# aqm_sch.net
KiCad netlist of a schematic drawn in EAGLE
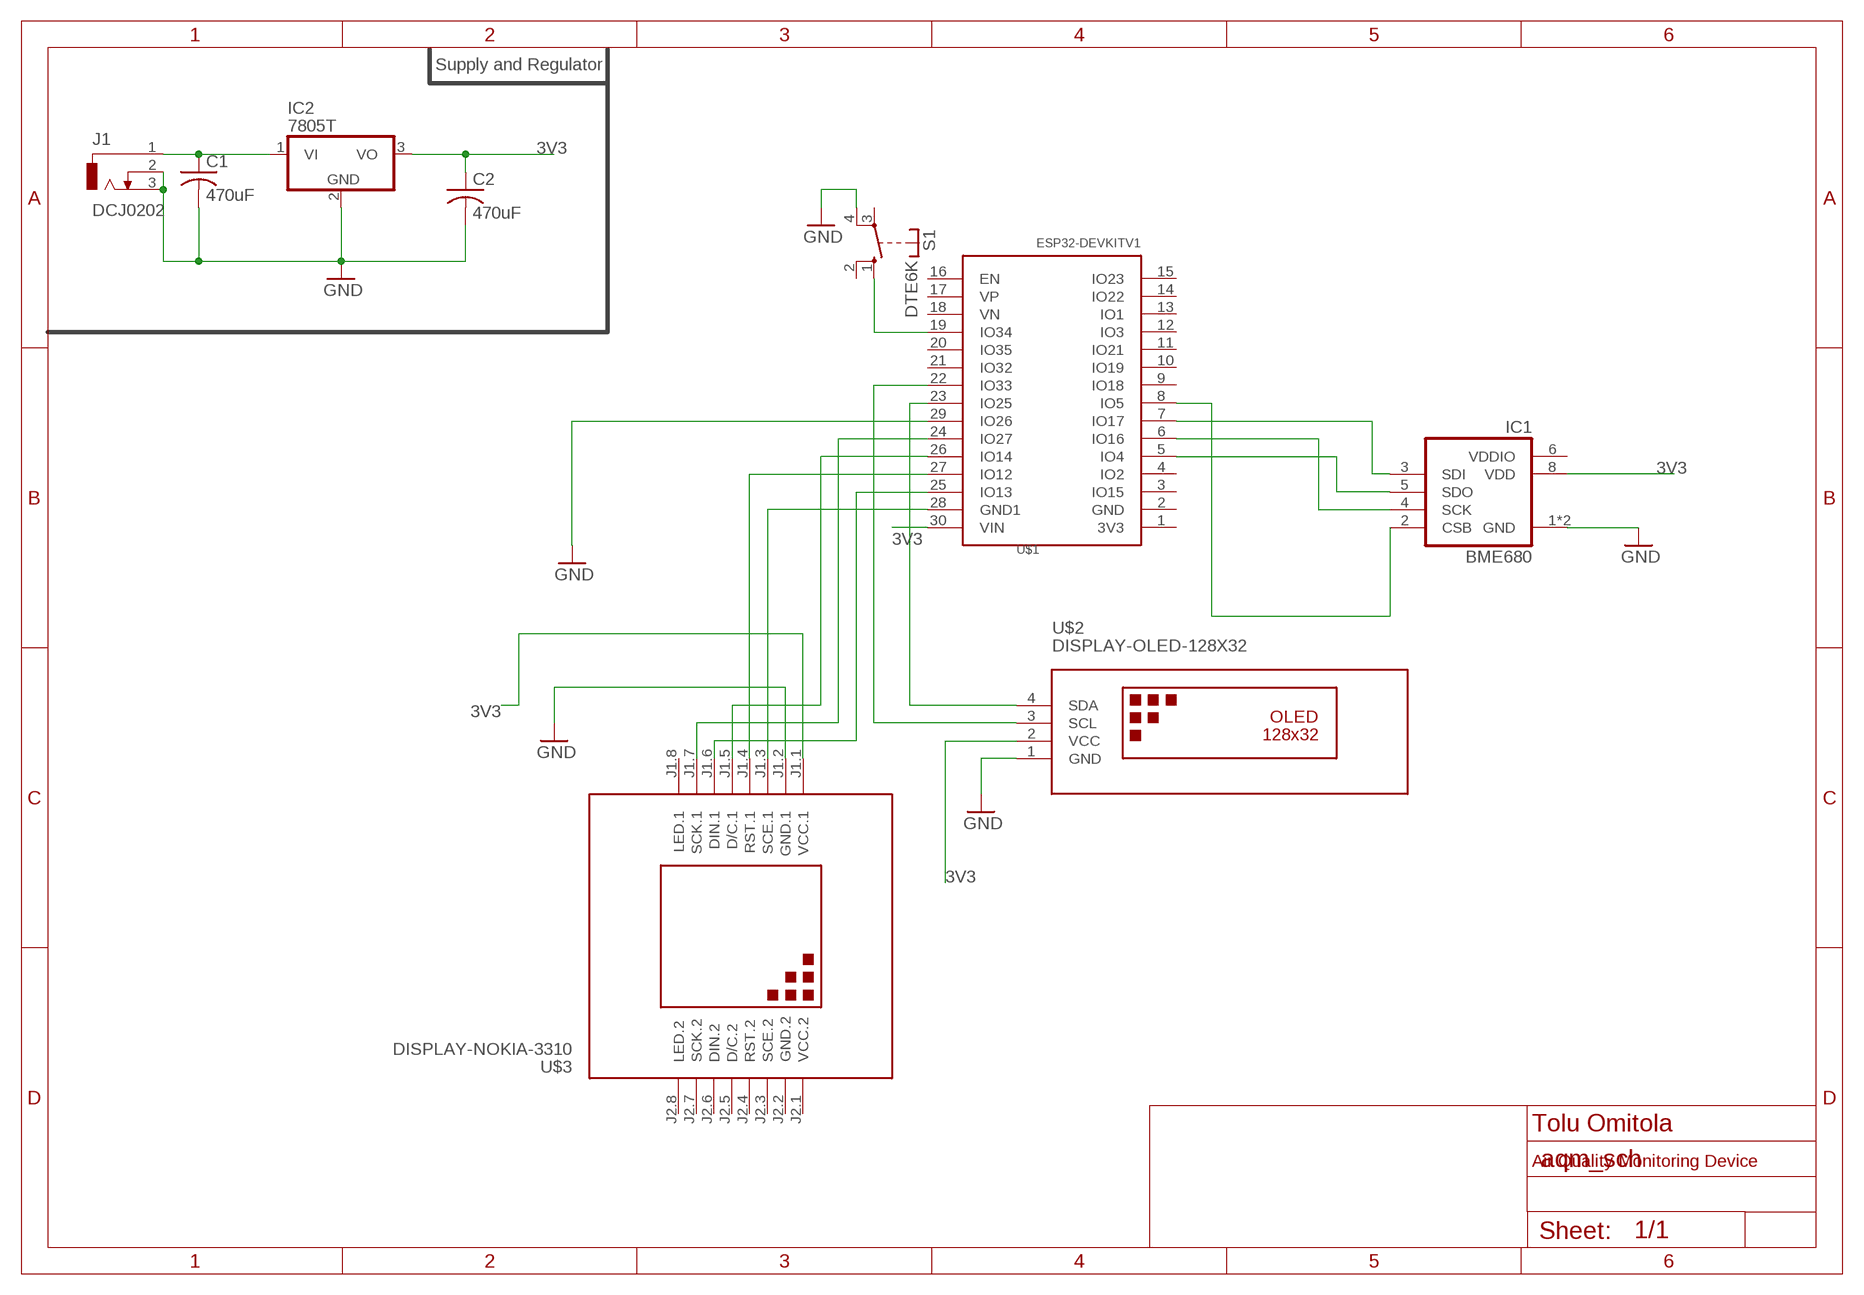
[diagram p0: schematic, sheet 1]

(export (version "E")
  (design (tool "Eeschema 10.0.6"))
  (components
    (comp (ref "C1")
      (value "470uF")
      (footprint "eagle-import:C075-052X106")
      (libsource (lib "eagle-import") (part "C-US075-052X106"))
    )
    (comp (ref "C2")
      (value "470uF")
      (footprint "eagle-import:C075-052X106")
      (libsource (lib "eagle-import") (part "C-US075-052X106"))
    )
    (comp (ref "IC1")
      (value "BME680")
      (footprint "eagle-import:BME680")
      (libsource (lib "eagle-import") (part "BME680"))
    )
    (comp (ref "IC2")
      (value "7805T")
      (footprint "eagle-import:TO220H")
      (libsource (lib "eagle-import") (part "78T05"))
    )
    (comp (ref "J1")
      (value "DCJ0202")
      (footprint "eagle-import:DCJ0202")
      (libsource (lib "eagle-import") (part "DCJ0202"))
    )
    (comp (ref "S1")
      (value "DTE6K")
      (footprint "eagle-import:DTE6K")
      (libsource (lib "eagle-import") (part "DTE6K"))
    )
    (comp (ref "U$1")
      (value "ESP32DEVKITV1")
      (footprint "eagle-import:ESP32-DEVKITV1")
      (libsource (lib "eagle-import") (part "ESP32DEVKITV1"))
    )
    (comp (ref "U$2")
      (value "DISPLAY-OLED-128X32")
      (footprint "eagle-import:DISPLAY-OLED-128X32")
      (libsource (lib "eagle-import") (part "DISPLAY-OLED-128X32"))
    )
    (comp (ref "U$3")
      (value "DISPLAY-NOKIA-3310")
      (footprint "eagle-import:DISPLAY-NOKIA-3310")
      (libsource (lib "eagle-import") (part "DISPLAY-NOKIA-3310"))
    )
  )
  (nets
    (net (code "1") (name "/3V3") (class "Default")
      (node (ref "C2") (pin "1") (pinfunction "1_1") (pintype "passive"))
      (node (ref "IC1") (pin "8") (pinfunction "VDD_8") (pintype "power_in"))
      (node (ref "IC2") (pin "3") (pinfunction "VO_3") (pintype "passive"))
      (node (ref "U$1") (pin "30") (pinfunction "VIN_30") (pintype "bidirectional"))
      (node (ref "U$2") (pin "2") (pinfunction "VCC_2") (pintype "power_in"))
      (node (ref "U$3") (pin "J1.1") (pinfunction "VCC.1_J1.1") (pintype "power_in"))
    )
    (net (code "2") (name "/GND.2") (class "Default")
      (node (ref "U$3") (pin "J2.2") (pinfunction "GND.2_J2.2") (pintype "power_in"))
    )
    (net (code "3") (name "/VCC.2") (class "Default")
      (node (ref "U$3") (pin "J2.1") (pinfunction "VCC.2_J2.1") (pintype "power_in"))
    )
    (net (code "4") (name "/VDDIO") (class "Default")
      (node (ref "IC1") (pin "6") (pinfunction "VDDIO_6") (pintype "power_in"))
    )
    (net (code "5") (name "GND") (class "Default")
      (node (ref "C1") (pin "2") (pinfunction "2_2") (pintype "passive"))
      (node (ref "C2") (pin "2") (pinfunction "2_2") (pintype "passive"))
      (node (ref "IC1") (pin "1") (pinfunction "GND_1") (pintype "power_in"))
      (node (ref "IC1") (pin "7") (pinfunction "GND_7") (pintype "power_in"))
      (node (ref "IC2") (pin "2") (pinfunction "GND_2") (pintype "passive"))
      (node (ref "J1") (pin "2") (pinfunction "2_2") (pintype "passive"))
      (node (ref "J1") (pin "3") (pinfunction "3_3") (pintype "passive"))
      (node (ref "S1") (pin "4") (pinfunction "P_4") (pintype "passive"))
      (node (ref "U$1") (pin "29") (pinfunction "IO26_29") (pintype "bidirectional"))
      (node (ref "U$2") (pin "1") (pinfunction "GND_1") (pintype "power_in"))
      (node (ref "U$3") (pin "J1.2") (pinfunction "GND.1_J1.2") (pintype "power_in"))
    )
    (net (code "6") (name "Net-(IC1-CSB)") (class "Default")
      (node (ref "IC1") (pin "2") (pinfunction "CSB_2") (pintype "input"))
      (node (ref "U$1") (pin "8") (pinfunction "IO5_8") (pintype "bidirectional"))
    )
    (net (code "7") (name "Net-(IC1-SCK)") (class "Default")
      (node (ref "IC1") (pin "4") (pinfunction "SCK_4") (pintype "input"))
      (node (ref "U$1") (pin "6") (pinfunction "IO16_6") (pintype "bidirectional"))
    )
    (net (code "8") (name "Net-(IC1-SDI)") (class "Default")
      (node (ref "IC1") (pin "3") (pinfunction "SDI_3") (pintype "input"))
      (node (ref "U$1") (pin "7") (pinfunction "IO17_7") (pintype "bidirectional"))
    )
    (net (code "9") (name "Net-(IC1-SDO)") (class "Default")
      (node (ref "IC1") (pin "5") (pinfunction "SDO_5") (pintype "output"))
      (node (ref "U$1") (pin "5") (pinfunction "IO4_5") (pintype "bidirectional"))
    )
    (net (code "10") (name "Net-(IC2-VI)") (class "Default")
      (node (ref "C1") (pin "1") (pinfunction "1_1") (pintype "passive"))
      (node (ref "IC2") (pin "1") (pinfunction "VI_1") (pintype "input"))
      (node (ref "J1") (pin "1") (pinfunction "1_1") (pintype "passive"))
    )
    (net (code "11") (name "Net-(U$1-GND1)") (class "Default")
      (node (ref "U$1") (pin "28") (pinfunction "GND1_28") (pintype "bidirectional"))
      (node (ref "U$3") (pin "J1.3") (pinfunction "SCE.1_J1.3") (pintype "bidirectional"))
    )
    (net (code "12") (name "Net-(U$1-IO12)") (class "Default")
      (node (ref "U$1") (pin "27") (pinfunction "IO12_27") (pintype "bidirectional"))
      (node (ref "U$3") (pin "J1.4") (pinfunction "RST.1_J1.4") (pintype "bidirectional"))
    )
    (net (code "13") (name "Net-(U$1-IO13)") (class "Default")
      (node (ref "U$1") (pin "25") (pinfunction "IO13_25") (pintype "bidirectional"))
      (node (ref "U$3") (pin "J1.6") (pinfunction "DIN.1_J1.6") (pintype "bidirectional"))
    )
    (net (code "14") (name "Net-(U$1-IO14)") (class "Default")
      (node (ref "U$1") (pin "26") (pinfunction "IO14_26") (pintype "bidirectional"))
      (node (ref "U$3") (pin "J1.5") (pinfunction "D/C.1_J1.5") (pintype "bidirectional"))
    )
    (net (code "15") (name "Net-(U$1-IO25)") (class "Default")
      (node (ref "U$1") (pin "23") (pinfunction "IO25_23") (pintype "bidirectional"))
      (node (ref "U$2") (pin "4") (pinfunction "SDA_4") (pintype "bidirectional"))
    )
    (net (code "16") (name "Net-(U$1-IO27)") (class "Default")
      (node (ref "U$1") (pin "24") (pinfunction "IO27_24") (pintype "bidirectional"))
      (node (ref "U$3") (pin "J1.7") (pinfunction "SCK.1_J1.7") (pintype "bidirectional"))
    )
    (net (code "17") (name "Net-(U$1-IO33)") (class "Default")
      (node (ref "U$1") (pin "22") (pinfunction "IO33_22") (pintype "bidirectional"))
      (node (ref "U$2") (pin "3") (pinfunction "SCL_3") (pintype "bidirectional"))
    )
    (net (code "18") (name "Net-(U$1-IO34)") (class "Default")
      (node (ref "S1") (pin "1") (pinfunction "S_1") (pintype "passive"))
      (node (ref "U$1") (pin "19") (pinfunction "IO34_19") (pintype "bidirectional"))
    )
    (net (code "19") (name "unconnected-(S1-P-Pad3)") (class "Default")
      (node (ref "S1") (pin "3") (pinfunction "P_3") (pintype "passive"))
    )
    (net (code "20") (name "unconnected-(S1-S-Pad2)") (class "Default")
      (node (ref "S1") (pin "2") (pinfunction "S_2") (pintype "passive"))
    )
    (net (code "21") (name "unconnected-(U$1-3V3-Pad1)") (class "Default")
      (node (ref "U$1") (pin "1") (pinfunction "3V3_1") (pintype "bidirectional"))
    )
    (net (code "22") (name "unconnected-(U$1-EN-Pad16)") (class "Default")
      (node (ref "U$1") (pin "16") (pinfunction "EN_16") (pintype "bidirectional"))
    )
    (net (code "23") (name "unconnected-(U$1-GND-Pad2)") (class "Default")
      (node (ref "U$1") (pin "2") (pinfunction "GND_2") (pintype "bidirectional"))
    )
    (net (code "24") (name "unconnected-(U$1-IO1-Pad13)") (class "Default")
      (node (ref "U$1") (pin "13") (pinfunction "IO1_13") (pintype "bidirectional"))
    )
    (net (code "25") (name "unconnected-(U$1-IO2-Pad4)") (class "Default")
      (node (ref "U$1") (pin "4") (pinfunction "IO2_4") (pintype "bidirectional"))
    )
    (net (code "26") (name "unconnected-(U$1-IO3-Pad12)") (class "Default")
      (node (ref "U$1") (pin "12") (pinfunction "IO3_12") (pintype "bidirectional"))
    )
    (net (code "27") (name "unconnected-(U$1-IO15-Pad3)") (class "Default")
      (node (ref "U$1") (pin "3") (pinfunction "IO15_3") (pintype "bidirectional"))
    )
    (net (code "28") (name "unconnected-(U$1-IO18-Pad9)") (class "Default")
      (node (ref "U$1") (pin "9") (pinfunction "IO18_9") (pintype "bidirectional"))
    )
    (net (code "29") (name "unconnected-(U$1-IO19-Pad10)") (class "Default")
      (node (ref "U$1") (pin "10") (pinfunction "IO19_10") (pintype "bidirectional"))
    )
    (net (code "30") (name "unconnected-(U$1-IO21-Pad11)") (class "Default")
      (node (ref "U$1") (pin "11") (pinfunction "IO21_11") (pintype "bidirectional"))
    )
    (net (code "31") (name "unconnected-(U$1-IO22-Pad14)") (class "Default")
      (node (ref "U$1") (pin "14") (pinfunction "IO22_14") (pintype "bidirectional"))
    )
    (net (code "32") (name "unconnected-(U$1-IO23-Pad15)") (class "Default")
      (node (ref "U$1") (pin "15") (pinfunction "IO23_15") (pintype "bidirectional"))
    )
    (net (code "33") (name "unconnected-(U$1-IO32-Pad21)") (class "Default")
      (node (ref "U$1") (pin "21") (pinfunction "IO32_21") (pintype "bidirectional"))
    )
    (net (code "34") (name "unconnected-(U$1-IO35-Pad20)") (class "Default")
      (node (ref "U$1") (pin "20") (pinfunction "IO35_20") (pintype "bidirectional"))
    )
    (net (code "35") (name "unconnected-(U$1-VN-Pad18)") (class "Default")
      (node (ref "U$1") (pin "18") (pinfunction "VN_18") (pintype "bidirectional"))
    )
    (net (code "36") (name "unconnected-(U$1-VP-Pad17)") (class "Default")
      (node (ref "U$1") (pin "17") (pinfunction "VP_17") (pintype "bidirectional"))
    )
    (net (code "37") (name "unconnected-(U$3-DIN.2-PadJ2.6)") (class "Default")
      (node (ref "U$3") (pin "J2.6") (pinfunction "DIN.2_J2.6") (pintype "bidirectional"))
    )
    (net (code "38") (name "unconnected-(U$3-D{slash}C.2-PadJ2.5)") (class "Default")
      (node (ref "U$3") (pin "J2.5") (pinfunction "D/C.2_J2.5") (pintype "bidirectional"))
    )
    (net (code "39") (name "unconnected-(U$3-LED.1-PadJ1.8)") (class "Default")
      (node (ref "U$3") (pin "J1.8") (pinfunction "LED.1_J1.8") (pintype "input"))
    )
    (net (code "40") (name "unconnected-(U$3-LED.2-PadJ2.8)") (class "Default")
      (node (ref "U$3") (pin "J2.8") (pinfunction "LED.2_J2.8") (pintype "input"))
    )
    (net (code "41") (name "unconnected-(U$3-RST.2-PadJ2.4)") (class "Default")
      (node (ref "U$3") (pin "J2.4") (pinfunction "RST.2_J2.4") (pintype "bidirectional"))
    )
    (net (code "42") (name "unconnected-(U$3-SCE.2-PadJ2.3)") (class "Default")
      (node (ref "U$3") (pin "J2.3") (pinfunction "SCE.2_J2.3") (pintype "bidirectional"))
    )
    (net (code "43") (name "unconnected-(U$3-SCK.2-PadJ2.7)") (class "Default")
      (node (ref "U$3") (pin "J2.7") (pinfunction "SCK.2_J2.7") (pintype "bidirectional"))
    )
  )
)
